# placa_painel.net
KiCad netlist of a schematic drawn in EAGLE
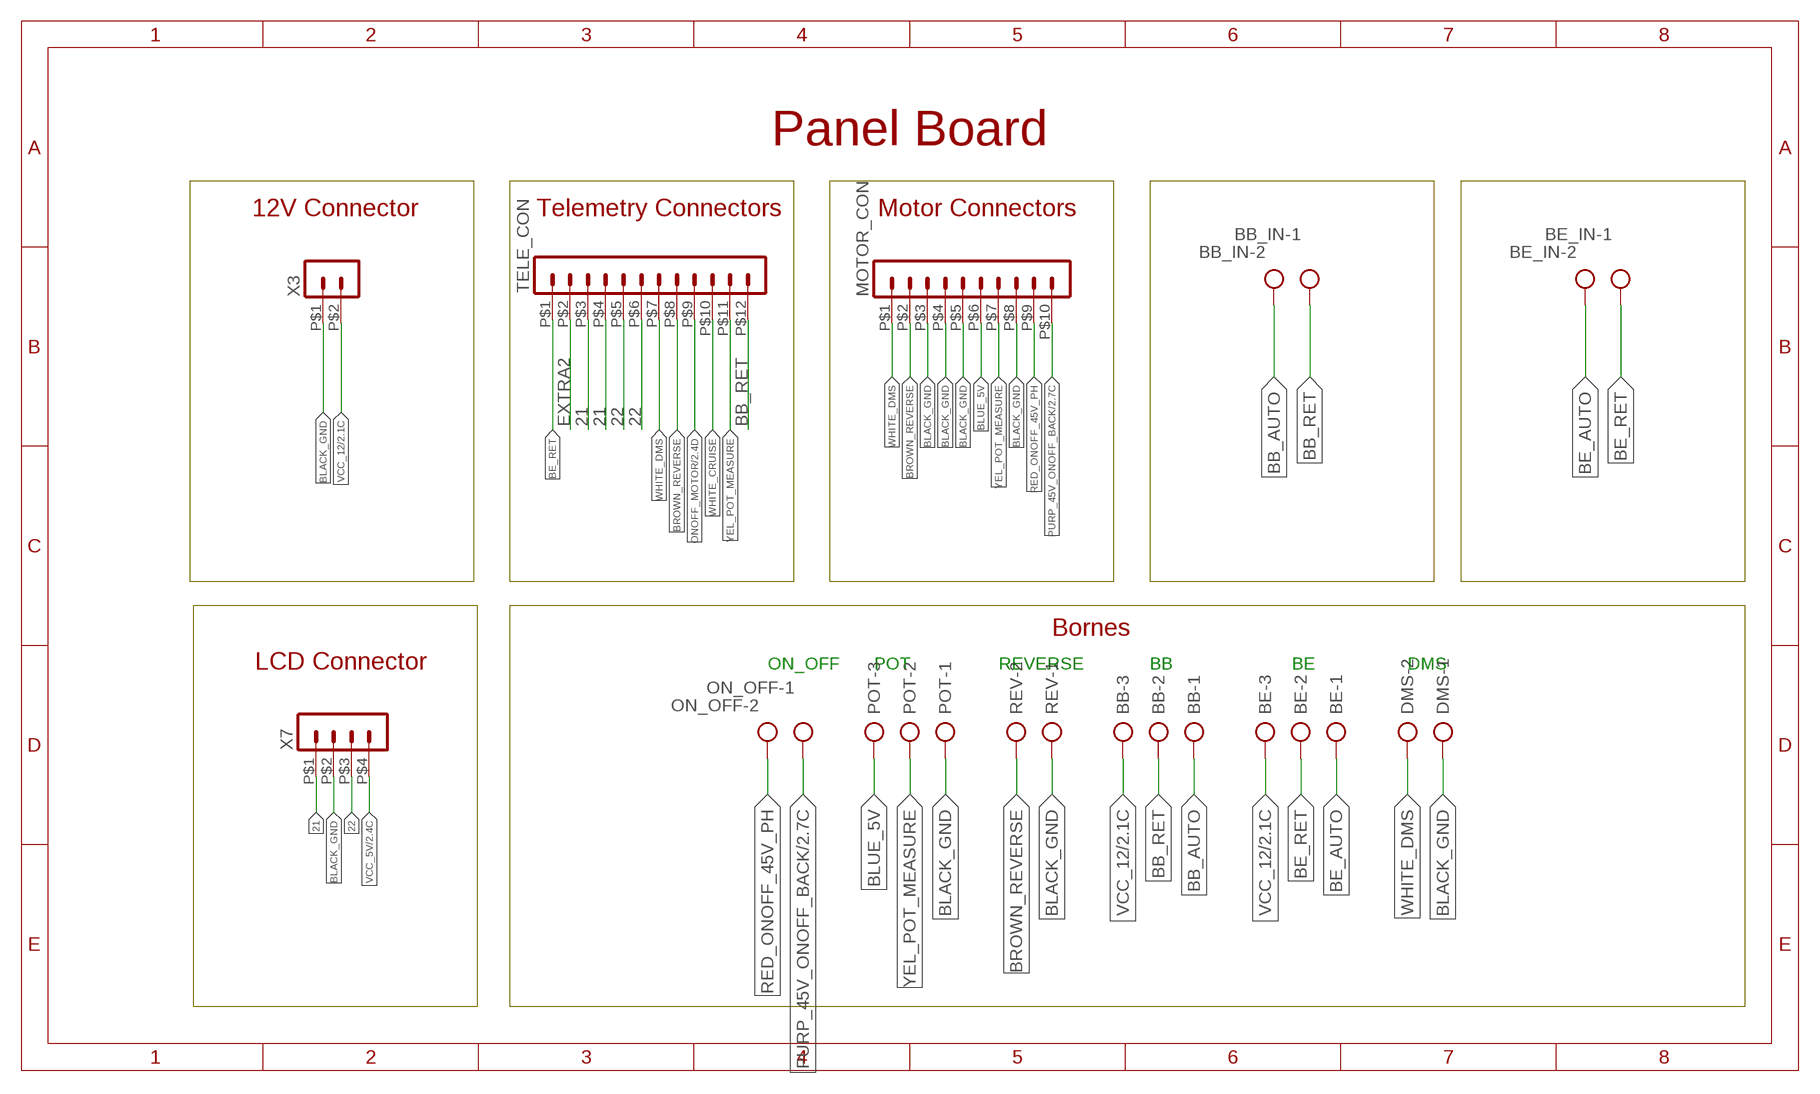
[diagram p0: schematic, sheet 1]
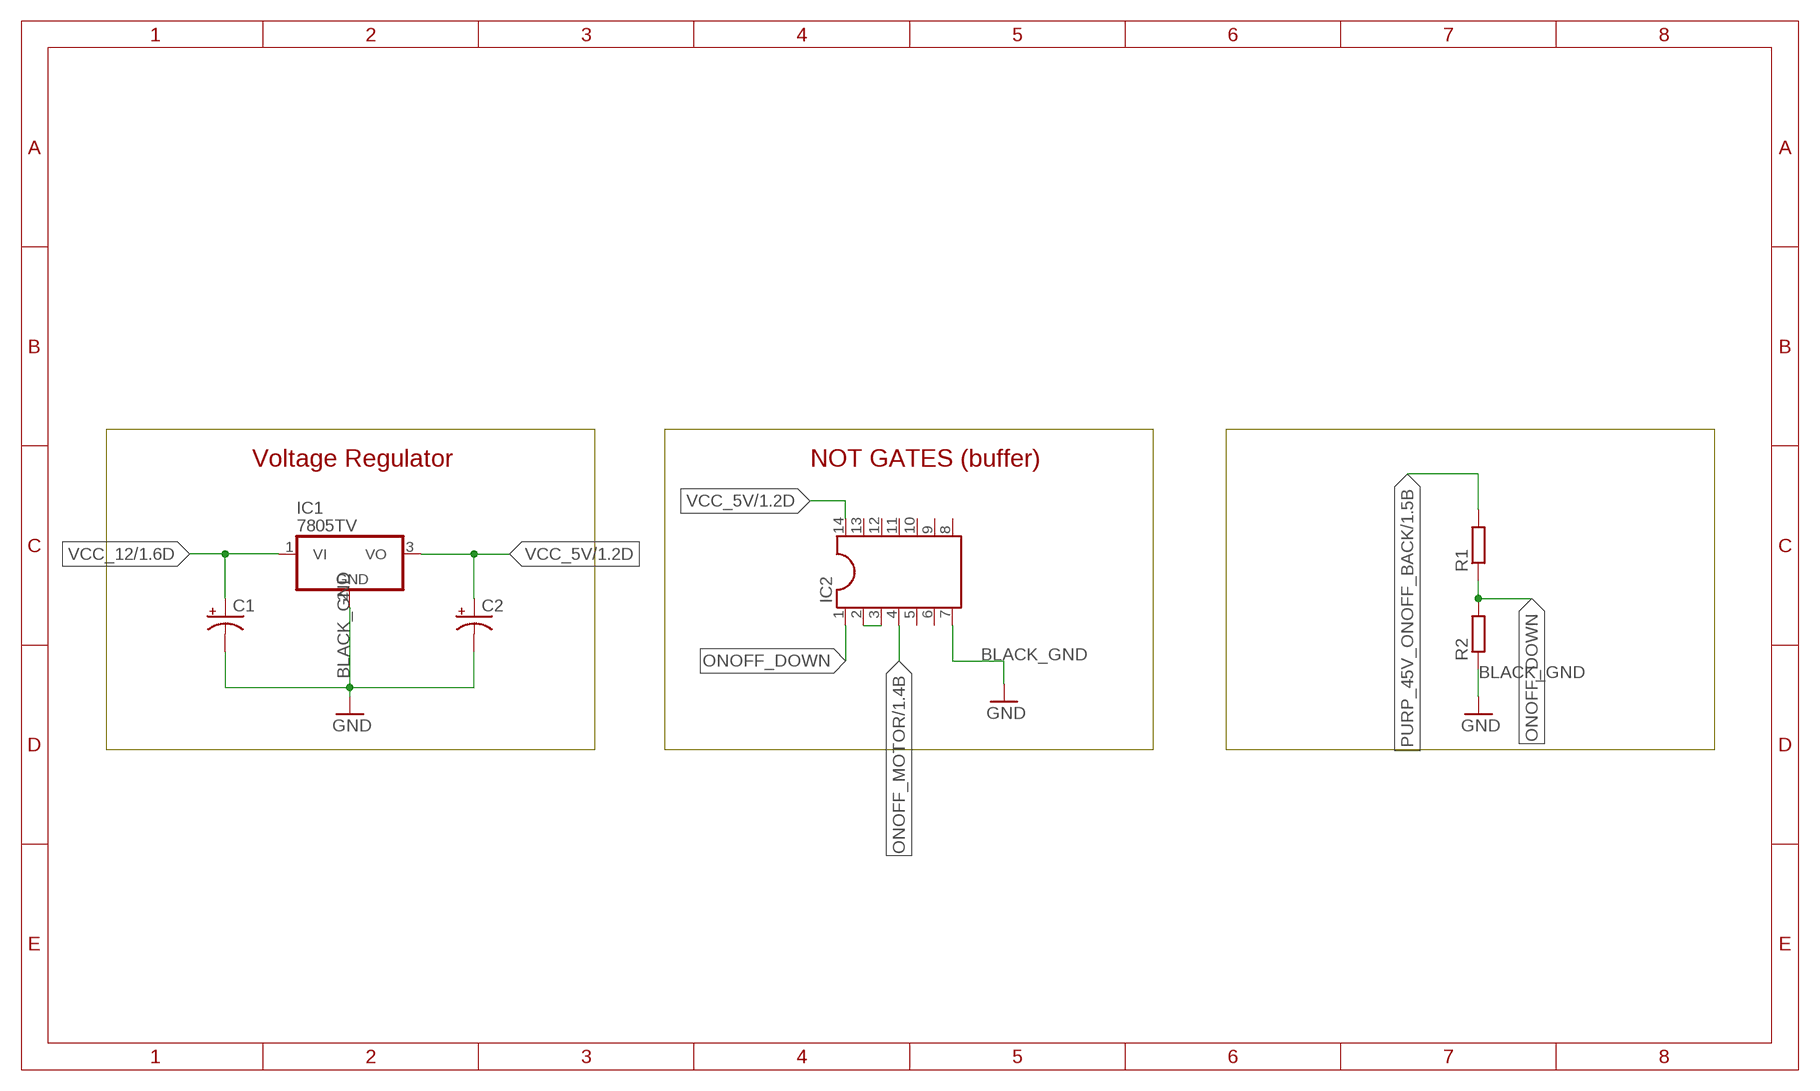
[diagram p1: schematic, sheet 2]

(export (version "E")
  (design (tool "Eeschema 10.0.6"))
  (components
    (comp (ref "C1")
      (value "CPOL-USE5-5")
      (footprint "eagle-import:E5-5")
      (libsource (lib "eagle-import") (part "CPOL-USE5-5"))
    )
    (comp (ref "C2")
      (value "CPOL-USE5-5")
      (footprint "eagle-import:E5-5")
      (libsource (lib "eagle-import") (part "CPOL-USE5-5"))
    )
    (comp (ref "IC1")
      (value "7805TV")
      (footprint "eagle-import:TO220V")
      (libsource (lib "eagle-import") (part "78TV05"))
    )
    (comp (ref "IC2")
      (value "DIL14")
      (footprint "eagle-import:DIL14")
      (libsource (lib "eagle-import") (part "DIL14"))
    )
    (comp (ref "R1")
      (value "R-EU_0204/7")
      (footprint "eagle-import:0204_7")
      (libsource (lib "eagle-import") (part "R-EU_0204/7"))
    )
    (comp (ref "R2")
      (value "R-EU_0204/7")
      (footprint "eagle-import:0204_7")
      (libsource (lib "eagle-import") (part "R-EU_0204/7"))
    )
    (comp (ref "BB")
      (value "AK500/3")
      (footprint "eagle-import:AK500_3")
      (libsource (lib "eagle-import") (part "AK500/3"))
    )
    (comp (ref "BB_IN")
      (value "AK500/2")
      (footprint "eagle-import:AK500_2")
      (libsource (lib "eagle-import") (part "AK500/2"))
    )
    (comp (ref "BE")
      (value "AK500/3")
      (footprint "eagle-import:AK500_3")
      (libsource (lib "eagle-import") (part "AK500/3"))
    )
    (comp (ref "BE_IN")
      (value "AK500/2")
      (footprint "eagle-import:AK500_2")
      (libsource (lib "eagle-import") (part "AK500/2"))
    )
    (comp (ref "DMS")
      (value "AK500/2")
      (footprint "eagle-import:AK500_2")
      (libsource (lib "eagle-import") (part "AK500/2"))
    )
    (comp (ref "MOTOR_CON")
      (value "HEADER_POS10_43045-1012")
      (footprint "eagle-import:43045-1012")
      (libsource (lib "eagle-import") (part "HEADER_POS10_?43045-1012"))
    )
    (comp (ref "ON_OFF")
      (value "AK500/2")
      (footprint "eagle-import:AK500_2")
      (libsource (lib "eagle-import") (part "AK500/2"))
    )
    (comp (ref "POT")
      (value "AK500/3")
      (footprint "eagle-import:AK500_3")
      (libsource (lib "eagle-import") (part "AK500/3"))
    )
    (comp (ref "REV")
      (value "AK500/2")
      (footprint "eagle-import:AK500_2")
      (libsource (lib "eagle-import") (part "AK500/2"))
    )
    (comp (ref "TELE_CON")
      (value "HEADER_POS12_43045-1212")
      (footprint "eagle-import:43045-1212")
      (libsource (lib "eagle-import") (part "HEADER_POS12_?43045-1212"))
    )
    (comp (ref "X3")
      (value "HEADER_POS2_43045-0212")
      (footprint "eagle-import:43045-0212")
      (libsource (lib "eagle-import") (part "HEADER_POS2_?43045-0212"))
    )
    (comp (ref "X7")
      (value "HEADER_POS4_43045-0412")
      (footprint "eagle-import:43045-0412")
      (libsource (lib "eagle-import") (part "HEADER_POS4_?43045-0412"))
    )
  )
  (nets
    (net (code "1") (name "21") (class "Default")
      (node (ref "TELE_CON") (pin "P$3") (pinfunction "3_P$3") (pintype "passive"))
      (node (ref "TELE_CON") (pin "P$4") (pinfunction "4_P$4") (pintype "passive"))
      (node (ref "X7") (pin "P$1") (pinfunction "1_P$1") (pintype "passive"))
    )
    (net (code "2") (name "22") (class "Default")
      (node (ref "TELE_CON") (pin "P$5") (pinfunction "5_P$5") (pintype "passive"))
      (node (ref "TELE_CON") (pin "P$6") (pinfunction "6_P$6") (pintype "passive"))
      (node (ref "X7") (pin "P$3") (pinfunction "3_P$3") (pintype "passive"))
    )
    (net (code "3") (name "BB_AUTO") (class "Default")
      (node (ref "BB") (pin "1") (pinfunction "KL_1") (pintype "passive"))
      (node (ref "BB_IN") (pin "2") (pinfunction "KL_2") (pintype "passive"))
    )
    (net (code "4") (name "BB_RET") (class "Default")
      (node (ref "BB") (pin "2") (pinfunction "KL_2") (pintype "passive"))
      (node (ref "BB_IN") (pin "1") (pinfunction "KL_1") (pintype "passive"))
      (node (ref "TELE_CON") (pin "P$12") (pinfunction "12_P$12") (pintype "passive"))
    )
    (net (code "5") (name "BE_AUTO") (class "Default")
      (node (ref "BE") (pin "1") (pinfunction "KL_1") (pintype "passive"))
      (node (ref "BE_IN") (pin "2") (pinfunction "KL_2") (pintype "passive"))
    )
    (net (code "6") (name "BE_RET") (class "Default")
      (node (ref "BE") (pin "2") (pinfunction "KL_2") (pintype "passive"))
      (node (ref "BE_IN") (pin "1") (pinfunction "KL_1") (pintype "passive"))
      (node (ref "TELE_CON") (pin "P$1") (pinfunction "1_P$1") (pintype "passive"))
    )
    (net (code "7") (name "BLACK_GND") (class "Default")
      (node (ref "C1") (pin "-") (pinfunction "-_-") (pintype "passive"))
      (node (ref "C2") (pin "-") (pinfunction "-_-") (pintype "passive"))
      (node (ref "DMS") (pin "1") (pinfunction "KL_1") (pintype "passive"))
      (node (ref "IC1") (pin "2") (pinfunction "GND_2") (pintype "passive"))
      (node (ref "IC2") (pin "7") (pinfunction "7_7") (pintype "passive"))
      (node (ref "MOTOR_CON") (pin "P$3") (pinfunction "3_P$3") (pintype "passive"))
      (node (ref "MOTOR_CON") (pin "P$4") (pinfunction "4_P$4") (pintype "passive"))
      (node (ref "MOTOR_CON") (pin "P$5") (pinfunction "5_P$5") (pintype "passive"))
      (node (ref "MOTOR_CON") (pin "P$8") (pinfunction "8_P$8") (pintype "passive"))
      (node (ref "POT") (pin "1") (pinfunction "KL_1") (pintype "passive"))
      (node (ref "R2") (pin "1") (pinfunction "1_1") (pintype "passive"))
      (node (ref "REV") (pin "1") (pinfunction "KL_1") (pintype "passive"))
      (node (ref "X3") (pin "P$1") (pinfunction "1_P$1") (pintype "passive"))
      (node (ref "X7") (pin "P$2") (pinfunction "2_P$2") (pintype "passive"))
    )
    (net (code "8") (name "BLUE_5V") (class "Default")
      (node (ref "MOTOR_CON") (pin "P$6") (pinfunction "6_P$6") (pintype "passive"))
      (node (ref "POT") (pin "3") (pinfunction "KL_3") (pintype "passive"))
    )
    (net (code "9") (name "BROWN_REVERSE") (class "Default")
      (node (ref "MOTOR_CON") (pin "P$2") (pinfunction "2_P$2") (pintype "passive"))
      (node (ref "REV") (pin "2") (pinfunction "KL_2") (pintype "passive"))
      (node (ref "TELE_CON") (pin "P$8") (pinfunction "8_P$8") (pintype "passive"))
    )
    (net (code "10") (name "EXTRA2") (class "Default")
      (node (ref "TELE_CON") (pin "P$2") (pinfunction "2_P$2") (pintype "passive"))
    )
    (net (code "11") (name "Net-(IC2-Pad2)") (class "Default")
      (node (ref "IC2") (pin "2") (pinfunction "2_2") (pintype "passive"))
      (node (ref "IC2") (pin "3") (pinfunction "3_3") (pintype "passive"))
    )
    (net (code "12") (name "ONOFF_DOWN") (class "Default")
      (node (ref "IC2") (pin "1") (pinfunction "1_1") (pintype "passive"))
      (node (ref "R1") (pin "1") (pinfunction "1_1") (pintype "passive"))
      (node (ref "R2") (pin "2") (pinfunction "2_2") (pintype "passive"))
    )
    (net (code "13") (name "ONOFF_MOTOR") (class "Default")
      (node (ref "IC2") (pin "4") (pinfunction "4_4") (pintype "passive"))
      (node (ref "TELE_CON") (pin "P$9") (pinfunction "9_P$9") (pintype "passive"))
    )
    (net (code "14") (name "PURP_45V_ONOFF_BACK") (class "Default")
      (node (ref "MOTOR_CON") (pin "P$10") (pinfunction "10_P$10") (pintype "passive"))
      (node (ref "ON_OFF") (pin "1") (pinfunction "KL_1") (pintype "passive"))
      (node (ref "R1") (pin "2") (pinfunction "2_2") (pintype "passive"))
    )
    (net (code "15") (name "RED_ONOFF_45V_PH") (class "Default")
      (node (ref "MOTOR_CON") (pin "P$9") (pinfunction "9_P$9") (pintype "passive"))
      (node (ref "ON_OFF") (pin "2") (pinfunction "KL_2") (pintype "passive"))
    )
    (net (code "16") (name "VCC_5V") (class "Default")
      (node (ref "C2") (pin "+") (pinfunction "+_+") (pintype "passive"))
      (node (ref "IC1") (pin "3") (pinfunction "VO_3") (pintype "passive"))
      (node (ref "IC2") (pin "14") (pinfunction "14_14") (pintype "passive"))
      (node (ref "X7") (pin "P$4") (pinfunction "4_P$4") (pintype "passive"))
    )
    (net (code "17") (name "VCC_12") (class "Default")
      (node (ref "BB") (pin "3") (pinfunction "KL_3") (pintype "passive"))
      (node (ref "BE") (pin "3") (pinfunction "KL_3") (pintype "passive"))
      (node (ref "C1") (pin "+") (pinfunction "+_+") (pintype "passive"))
      (node (ref "IC1") (pin "1") (pinfunction "VI_1") (pintype "input"))
      (node (ref "X3") (pin "P$2") (pinfunction "2_P$2") (pintype "passive"))
    )
    (net (code "18") (name "WHITE_CRUISE") (class "Default")
      (node (ref "TELE_CON") (pin "P$10") (pinfunction "10_P$10") (pintype "passive"))
    )
    (net (code "19") (name "WHITE_DMS") (class "Default")
      (node (ref "DMS") (pin "2") (pinfunction "KL_2") (pintype "passive"))
      (node (ref "MOTOR_CON") (pin "P$1") (pinfunction "1_P$1") (pintype "passive"))
      (node (ref "TELE_CON") (pin "P$7") (pinfunction "7_P$7") (pintype "passive"))
    )
    (net (code "20") (name "YEL_POT_MEASURE") (class "Default")
      (node (ref "MOTOR_CON") (pin "P$7") (pinfunction "7_P$7") (pintype "passive"))
      (node (ref "POT") (pin "2") (pinfunction "KL_2") (pintype "passive"))
      (node (ref "TELE_CON") (pin "P$11") (pinfunction "11_P$11") (pintype "passive"))
    )
    (net (code "21") (name "unconnected-(IC2-Pad5)") (class "Default")
      (node (ref "IC2") (pin "5") (pinfunction "5_5") (pintype "passive"))
    )
    (net (code "22") (name "unconnected-(IC2-Pad6)") (class "Default")
      (node (ref "IC2") (pin "6") (pinfunction "6_6") (pintype "passive"))
    )
    (net (code "23") (name "unconnected-(IC2-Pad8)") (class "Default")
      (node (ref "IC2") (pin "8") (pinfunction "8_8") (pintype "passive"))
    )
    (net (code "24") (name "unconnected-(IC2-Pad9)") (class "Default")
      (node (ref "IC2") (pin "9") (pinfunction "9_9") (pintype "passive"))
    )
    (net (code "25") (name "unconnected-(IC2-Pad10)") (class "Default")
      (node (ref "IC2") (pin "10") (pinfunction "10_10") (pintype "passive"))
    )
    (net (code "26") (name "unconnected-(IC2-Pad11)") (class "Default")
      (node (ref "IC2") (pin "11") (pinfunction "11_11") (pintype "passive"))
    )
    (net (code "27") (name "unconnected-(IC2-Pad12)") (class "Default")
      (node (ref "IC2") (pin "12") (pinfunction "12_12") (pintype "passive"))
    )
    (net (code "28") (name "unconnected-(IC2-Pad13)") (class "Default")
      (node (ref "IC2") (pin "13") (pinfunction "13_13") (pintype "passive"))
    )
  )
)
